# design.net
KiCad netlist of a schematic drawn in Altium Designer
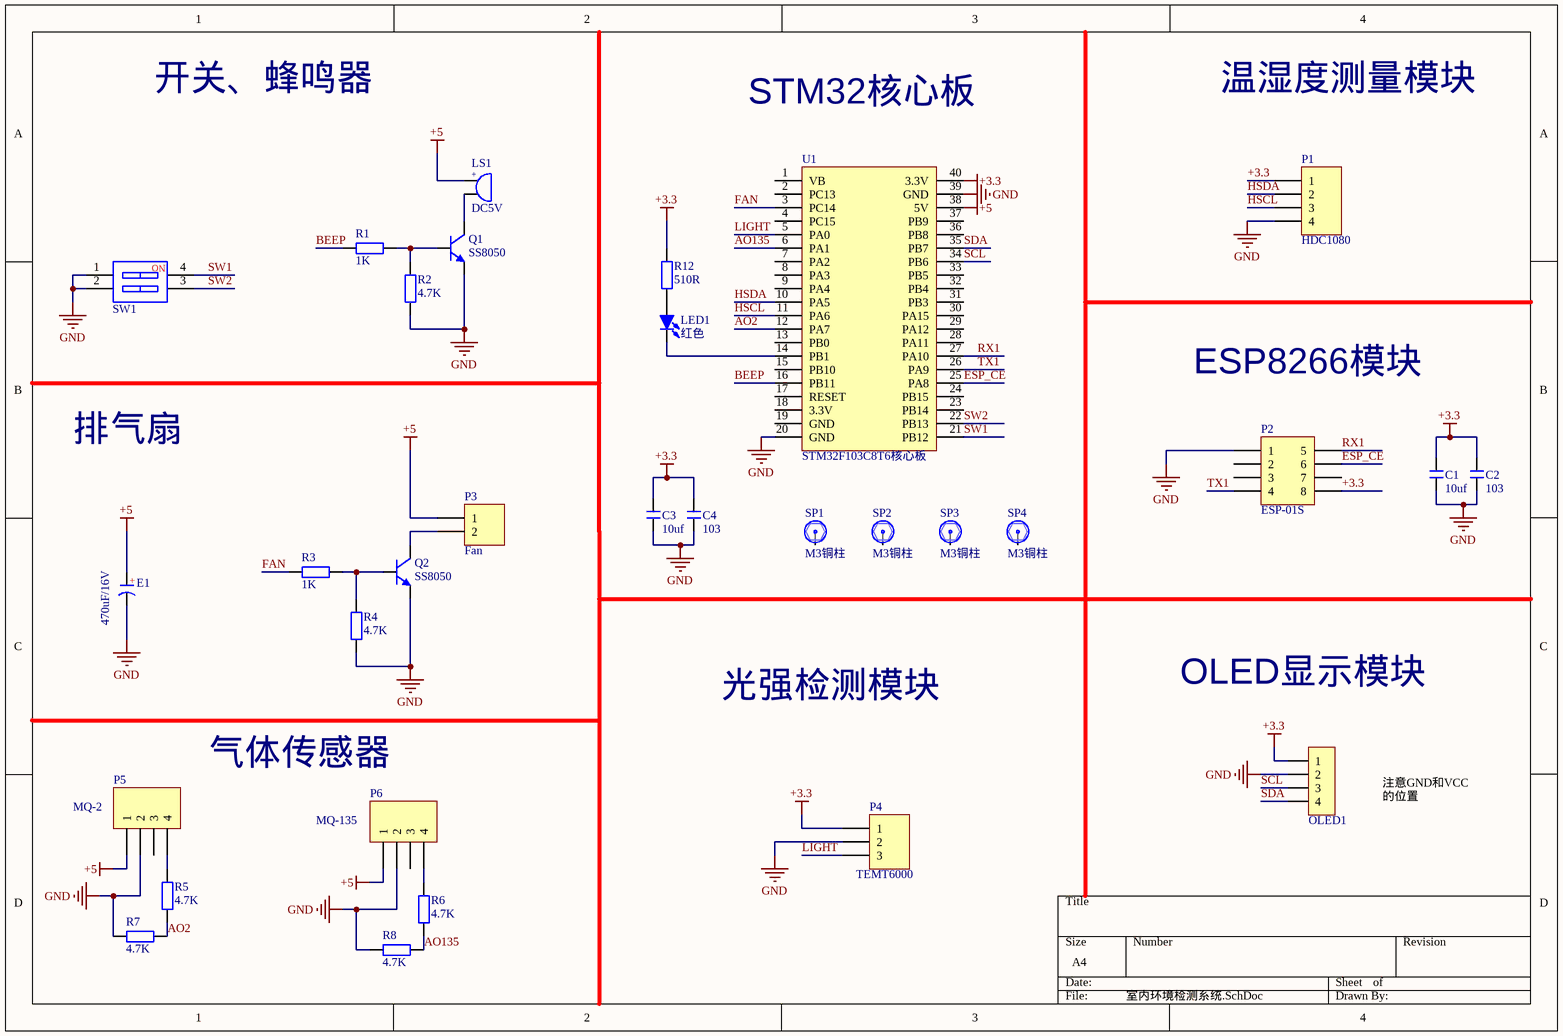
[diagram p0: 室内环境检测系统.SchDoc]

(export (version "E")
  (design (tool "Eeschema 10.0.6"))
  (components
    (comp (ref "C1")
      (value "10uf")
      (footprint "R 0805_M")
      (description "直插瓷片电容")
      (fields (field (name "版权归属") "源创客"))
      (libsource (lib "3.1   - 电阻-电容-电感") (part "C-CC"))
    )
    (comp (ref "C2")
      (value "103")
      (footprint "R 0805_M")
      (description "直插瓷片电容")
      (fields (field (name "版权归属") "源创客"))
      (libsource (lib "3.1   - 电阻-电容-电感") (part "C-CC"))
    )
    (comp (ref "C3")
      (value "10uf")
      (footprint "R 0805_M")
      (description "直插瓷片电容")
      (fields (field (name "版权归属") "源创客"))
      (libsource (lib "3.1   - 电阻-电容-电感") (part "C-CC"))
    )
    (comp (ref "C4")
      (value "103")
      (footprint "R 0805_M")
      (description "直插瓷片电容")
      (fields (field (name "版权归属") "源创客"))
      (libsource (lib "3.1   - 电阻-电容-电感") (part "C-CC"))
    )
    (comp (ref "E1")
      (value "470uF/16V")
      (footprint "CAP 2.0*5*11 - BK")
      (description "直插电解电容")
      (fields (field (name "版权归属") "源创客"))
      (libsource (lib "3.1   - 电阻-电容-电感") (part "C-CAP"))
    )
    (comp (ref "LED1")
      (value "红色")
      (footprint "LED 0805R")
      (description "贴片LED")
      (fields (field (name "版权归属") "源创客"))
      (libsource (lib "9.1   - LED") (part "LED-SMD"))
    )
    (comp (ref "LS1")
      (value "DC5V")
      (footprint "BEEP 5x9x5.5")
      (description "蜂鸣器")
      (fields (field (name "版权归属") "源创客"))
      (libsource (lib "15.1 - 未分类器件") (part "BEEP"))
    )
    (comp (ref "OLED1")
      (value "HDR-1X4")
      (footprint "HDR2.54-M-LI-4P")
      (description "4P接插件")
      (fields (field (name "版权归属") "源创客"))
      (libsource (lib "4.5   - 接插件-脚距2.54") (part "Header 4"))
    )
    (comp (ref "P1")
      (value "HDC1080")
      (footprint "HDR1X4")
      (description "Header, 4-Pin")
      (fields (field (name "PUBLISHER") "Altium Limited"))
      (libsource (lib "") (part "Header 4_1"))
    )
    (comp (ref "P2")
      (value "ESP-01S")
      (footprint "HDR2X4_CEN")
      (description "Header, 4-Pin, Dual row")
      (fields (field (name "PUBLISHER") "Altium Limited"))
      (libsource (lib "Miscellaneous Connectors") (part "Header 4X2A"))
    )
    (comp (ref "P3")
      (value "Fan")
      (footprint "HDR1X2H")
      (description "Header, 2-Pin, Right Angle")
      (fields (field (name "PUBLISHER") "Altium Limited"))
      (libsource (lib "Miscellaneous Connectors") (part "Header 2H"))
    )
    (comp (ref "P4")
      (value "TEMT6000")
      (footprint "HDR1X3")
      (description "Header, 3-Pin")
      (fields (field (name "PUBLISHER") "Altium Limited"))
      (libsource (lib "Miscellaneous Connectors") (part "Header 3"))
    )
    (comp (ref "P5")
      (value "MQ-2")
      (footprint "HDR1X4")
      (description "Header, 4-Pin")
      (fields (field (name "PUBLISHER") "Altium Limited"))
      (libsource (lib "Miscellaneous Connectors") (part "Header 4"))
    )
    (comp (ref "P6")
      (value "MQ-135")
      (footprint "HDR1X4")
      (description "Header, 4-Pin")
      (fields (field (name "PUBLISHER") "Altium Limited"))
      (libsource (lib "Miscellaneous Connectors") (part "Header 4"))
    )
    (comp (ref "Q1")
      (value "SS8050")
      (footprint "TO92A")
      (description "高频放大-NPN型")
      (fields (field (name "版权归属") "源创客"))
      (libsource (lib "6.2   - 三极管") (part "8050-DIP"))
    )
    (comp (ref "Q2")
      (value "SS8050")
      (footprint "TO92A")
      (description "高频放大-NPN型")
      (fields (field (name "版权归属") "源创客"))
      (libsource (lib "6.2   - 三极管") (part "8050-DIP"))
    )
    (comp (ref "R1")
      (value "1K")
      (footprint "R 0805_M")
      (description "直插色环电阻")
      (fields (field (name "版权归属") "源创客"))
      (libsource (lib "3.1   - 电阻-电容-电感") (part "R-CRR"))
    )
    (comp (ref "R2")
      (value "4.7K")
      (footprint "R 0805_M")
      (description "直插色环电阻")
      (fields (field (name "版权归属") "源创客"))
      (libsource (lib "3.1   - 电阻-电容-电感") (part "R-CRR"))
    )
    (comp (ref "R3")
      (value "1K")
      (footprint "R 0805_M")
      (description "直插色环电阻")
      (fields (field (name "版权归属") "源创客"))
      (libsource (lib "3.1   - 电阻-电容-电感") (part "R-CRR"))
    )
    (comp (ref "R4")
      (value "4.7K")
      (footprint "R 0805_M")
      (description "直插色环电阻")
      (fields (field (name "版权归属") "源创客"))
      (libsource (lib "3.1   - 电阻-电容-电感") (part "R-CRR"))
    )
    (comp (ref "R5")
      (value "4.7K")
      (footprint "R 0805_M")
      (description "直插色环电阻")
      (fields (field (name "版权归属") "源创客"))
      (libsource (lib "3.1   - 电阻-电容-电感") (part "R-CRR"))
    )
    (comp (ref "R6")
      (value "4.7K")
      (footprint "R 0805_M")
      (description "直插色环电阻")
      (fields (field (name "版权归属") "源创客"))
      (libsource (lib "3.1   - 电阻-电容-电感") (part "R-CRR"))
    )
    (comp (ref "R7")
      (value "4.7K")
      (footprint "R 0805_M")
      (description "直插色环电阻")
      (fields (field (name "版权归属") "源创客"))
      (libsource (lib "3.1   - 电阻-电容-电感") (part "R-CRR"))
    )
    (comp (ref "R8")
      (value "4.7K")
      (footprint "R 0805_M")
      (description "直插色环电阻")
      (fields (field (name "版权归属") "源创客"))
      (libsource (lib "3.1   - 电阻-电容-电感") (part "R-CRR"))
    )
    (comp (ref "R12")
      (value "510R")
      (footprint "R 0805_M")
      (description "直插色环电阻")
      (fields (field (name "版权归属") "源创客"))
      (libsource (lib "3.1   - 电阻-电容-电感") (part "R-CRR"))
    )
    (comp (ref "SP1")
      (value "M3铜柱")
      (footprint "M3x4_L")
      (description "铜柱")
      (fields (field (name "版权归属") "源创客"))
      (libsource (lib "15.1 - 未分类器件") (part "铜柱小焊盘"))
    )
    (comp (ref "SP2")
      (value "M3铜柱")
      (footprint "M3x4_L")
      (description "铜柱")
      (fields (field (name "版权归属") "源创客"))
      (libsource (lib "15.1 - 未分类器件") (part "铜柱小焊盘"))
    )
    (comp (ref "SP3")
      (value "M3铜柱")
      (footprint "M3x4_L")
      (description "铜柱")
      (fields (field (name "版权归属") "源创客"))
      (libsource (lib "15.1 - 未分类器件") (part "铜柱小焊盘"))
    )
    (comp (ref "SP4")
      (value "M3铜柱")
      (footprint "M3x4_L")
      (description "铜柱")
      (fields (field (name "版权归属") "源创客"))
      (libsource (lib "15.1 - 未分类器件") (part "铜柱小焊盘"))
    )
    (comp (ref "SW1")
      (value "CSW-2P")
      (footprint "CSW DIP-2P")
      (description "2路编码开关")
      (fields (field (name "版权归属") "源创客"))
      (libsource (lib "5.1   - 按键-开关") (part "CSW-2P"))
    )
    (comp (ref "U1")
      (value "STM32F103C8T6核心板")
      (footprint "DIP40-600_MH")
      (libsource (lib "STM32F103C8T6核心板") (part "STM32F103C8T6核心板"))
    )
  )
  (nets
    (net (code "1") (name "+3.3") (class "Default")
      (node (ref "C1") (pin "1") (pinfunction "1_1") (pintype "passive"))
      (node (ref "C2") (pin "1") (pinfunction "1_1") (pintype "passive"))
      (node (ref "C3") (pin "1") (pinfunction "1_1") (pintype "passive"))
      (node (ref "C4") (pin "1") (pinfunction "1_1") (pintype "passive"))
      (node (ref "OLED1") (pin "1") (pinfunction "1_1") (pintype "passive"))
      (node (ref "P1") (pin "1") (pinfunction "1_1") (pintype "passive"))
      (node (ref "P2") (pin "8") (pinfunction "8_8") (pintype "passive"))
      (node (ref "P4") (pin "1") (pinfunction "1_1") (pintype "passive"))
      (node (ref "R12") (pin "2") (pinfunction "2_2") (pintype "passive"))
      (node (ref "U1") (pin "40") (pinfunction "3.3V_40") (pintype "passive"))
    )
    (net (code "2") (name "+5") (class "Default")
      (node (ref "E1") (pin "1") (pinfunction "A_1") (pintype "passive"))
      (node (ref "LS1") (pin "1") (pinfunction "1_1") (pintype "passive"))
      (node (ref "P3") (pin "1") (pinfunction "1_1") (pintype "passive"))
      (node (ref "P5") (pin "1") (pinfunction "1_1") (pintype "passive"))
      (node (ref "P6") (pin "1") (pinfunction "1_1") (pintype "passive"))
      (node (ref "U1") (pin "38") (pinfunction "5V_38") (pintype "passive"))
    )
    (net (code "3") (name "/AO2") (class "Default")
      (node (ref "R5") (pin "2") (pinfunction "2_2") (pintype "passive"))
      (node (ref "R7") (pin "1") (pinfunction "1_1") (pintype "passive"))
      (node (ref "U1") (pin "12") (pinfunction "PA7_12") (pintype "passive"))
    )
    (net (code "4") (name "/AO135") (class "Default")
      (node (ref "R6") (pin "2") (pinfunction "2_2") (pintype "passive"))
      (node (ref "R8") (pin "1") (pinfunction "1_1") (pintype "passive"))
      (node (ref "U1") (pin "6") (pinfunction "PA1_6") (pintype "passive"))
    )
    (net (code "5") (name "/BEEP") (class "Default")
      (node (ref "R1") (pin "1") (pinfunction "1_1") (pintype "passive"))
      (node (ref "U1") (pin "16") (pinfunction "PB11_16") (pintype "passive"))
    )
    (net (code "6") (name "/ESP_CE") (class "Default")
      (node (ref "P2") (pin "6") (pinfunction "6_6") (pintype "passive"))
      (node (ref "U1") (pin "25") (pinfunction "PA8_25") (pintype "passive"))
    )
    (net (code "7") (name "/FAN") (class "Default")
      (node (ref "R3") (pin "1") (pinfunction "1_1") (pintype "passive"))
      (node (ref "U1") (pin "3") (pinfunction "PC14_3") (pintype "passive"))
    )
    (net (code "8") (name "/HSCL") (class "Default")
      (node (ref "P1") (pin "3") (pinfunction "3_3") (pintype "passive"))
      (node (ref "U1") (pin "11") (pinfunction "PA6_11") (pintype "passive"))
    )
    (net (code "9") (name "/HSDA") (class "Default")
      (node (ref "P1") (pin "2") (pinfunction "2_2") (pintype "passive"))
      (node (ref "U1") (pin "10") (pinfunction "PA5_10") (pintype "passive"))
    )
    (net (code "10") (name "/LIGHT") (class "Default")
      (node (ref "P4") (pin "3") (pinfunction "3_3") (pintype "passive"))
      (node (ref "U1") (pin "5") (pinfunction "PA0_5") (pintype "passive"))
    )
    (net (code "11") (name "/RX1") (class "Default")
      (node (ref "P2") (pin "5") (pinfunction "5_5") (pintype "passive"))
      (node (ref "U1") (pin "27") (pinfunction "PA10_27") (pintype "passive"))
    )
    (net (code "12") (name "/SCL") (class "Default")
      (node (ref "OLED1") (pin "3") (pinfunction "3_3") (pintype "passive"))
      (node (ref "U1") (pin "34") (pinfunction "PB6_34") (pintype "passive"))
    )
    (net (code "13") (name "/SDA") (class "Default")
      (node (ref "OLED1") (pin "4") (pinfunction "4_4") (pintype "passive"))
      (node (ref "U1") (pin "35") (pinfunction "PB7_35") (pintype "passive"))
    )
    (net (code "14") (name "/SW1") (class "Default")
      (node (ref "SW1") (pin "4") (pinfunction "4_4") (pintype "passive"))
      (node (ref "U1") (pin "21") (pinfunction "PB12_21") (pintype "passive"))
    )
    (net (code "15") (name "/SW2") (class "Default")
      (node (ref "SW1") (pin "3") (pinfunction "3_3") (pintype "passive"))
      (node (ref "U1") (pin "22") (pinfunction "PB13_22") (pintype "passive"))
    )
    (net (code "16") (name "/TX1") (class "Default")
      (node (ref "P2") (pin "4") (pinfunction "4_4") (pintype "passive"))
      (node (ref "U1") (pin "26") (pinfunction "PA9_26") (pintype "passive"))
    )
    (net (code "17") (name "GND") (class "Default")
      (node (ref "C1") (pin "2") (pinfunction "2_2") (pintype "passive"))
      (node (ref "C2") (pin "2") (pinfunction "2_2") (pintype "passive"))
      (node (ref "C3") (pin "2") (pinfunction "2_2") (pintype "passive"))
      (node (ref "C4") (pin "2") (pinfunction "2_2") (pintype "passive"))
      (node (ref "E1") (pin "2") (pinfunction "K_2") (pintype "passive"))
      (node (ref "OLED1") (pin "2") (pinfunction "2_2") (pintype "passive"))
      (node (ref "P1") (pin "4") (pinfunction "4_4") (pintype "passive"))
      (node (ref "P2") (pin "1") (pinfunction "1_1") (pintype "passive"))
      (node (ref "P4") (pin "2") (pinfunction "2_2") (pintype "passive"))
      (node (ref "P5") (pin "2") (pinfunction "2_2") (pintype "passive"))
      (node (ref "P6") (pin "2") (pinfunction "2_2") (pintype "passive"))
      (node (ref "Q1") (pin "1") (pinfunction "E_1") (pintype "passive"))
      (node (ref "Q2") (pin "1") (pinfunction "E_1") (pintype "passive"))
      (node (ref "R2") (pin "1") (pinfunction "1_1") (pintype "passive"))
      (node (ref "R4") (pin "1") (pinfunction "1_1") (pintype "passive"))
      (node (ref "R7") (pin "2") (pinfunction "2_2") (pintype "passive"))
      (node (ref "R8") (pin "2") (pinfunction "2_2") (pintype "passive"))
      (node (ref "SW1") (pin "1") (pinfunction "1_1") (pintype "passive"))
      (node (ref "SW1") (pin "2") (pinfunction "2_2") (pintype "passive"))
      (node (ref "U1") (pin "20") (pinfunction "GND_20") (pintype "passive"))
      (node (ref "U1") (pin "39") (pinfunction "GND_39") (pintype "passive"))
    )
    (net (code "18") (name "Net-(LED1-A)") (class "Default")
      (node (ref "LED1") (pin "1") (pinfunction "A_1") (pintype "passive"))
      (node (ref "R12") (pin "1") (pinfunction "1_1") (pintype "passive"))
    )
    (net (code "19") (name "Net-(LED1-K)") (class "Default")
      (node (ref "LED1") (pin "2") (pinfunction "K_2") (pintype "passive"))
      (node (ref "U1") (pin "14") (pinfunction "PB1_14") (pintype "passive"))
    )
    (net (code "20") (name "Net-(P5-Pad4)") (class "Default")
      (node (ref "P5") (pin "4") (pinfunction "4_4") (pintype "passive"))
      (node (ref "R5") (pin "1") (pinfunction "1_1") (pintype "passive"))
    )
    (net (code "21") (name "Net-(P6-Pad4)") (class "Default")
      (node (ref "P6") (pin "4") (pinfunction "4_4") (pintype "passive"))
      (node (ref "R6") (pin "1") (pinfunction "1_1") (pintype "passive"))
    )
    (net (code "22") (name "Net-(Q1-B)") (class "Default")
      (node (ref "Q1") (pin "2") (pinfunction "B_2") (pintype "passive"))
      (node (ref "R1") (pin "2") (pinfunction "2_2") (pintype "passive"))
      (node (ref "R2") (pin "2") (pinfunction "2_2") (pintype "passive"))
    )
    (net (code "23") (name "Net-(Q1-C)") (class "Default")
      (node (ref "LS1") (pin "2") (pinfunction "2_2") (pintype "passive"))
      (node (ref "Q1") (pin "3") (pinfunction "C_3") (pintype "passive"))
    )
    (net (code "24") (name "Net-(Q2-B)") (class "Default")
      (node (ref "Q2") (pin "2") (pinfunction "B_2") (pintype "passive"))
      (node (ref "R3") (pin "2") (pinfunction "2_2") (pintype "passive"))
      (node (ref "R4") (pin "2") (pinfunction "2_2") (pintype "passive"))
    )
    (net (code "25") (name "Net-(Q2-C)") (class "Default")
      (node (ref "P3") (pin "2") (pinfunction "2_2") (pintype "passive"))
      (node (ref "Q2") (pin "3") (pinfunction "C_3") (pintype "passive"))
    )
    (net (code "26") (name "unconnected-(P2-Pad2)") (class "Default")
      (node (ref "P2") (pin "2") (pinfunction "2_2") (pintype "passive"))
    )
    (net (code "27") (name "unconnected-(P2-Pad3)") (class "Default")
      (node (ref "P2") (pin "3") (pinfunction "3_3") (pintype "passive"))
    )
    (net (code "28") (name "unconnected-(P2-Pad7)") (class "Default")
      (node (ref "P2") (pin "7") (pinfunction "7_7") (pintype "passive"))
    )
    (net (code "29") (name "unconnected-(P5-Pad3)") (class "Default")
      (node (ref "P5") (pin "3") (pinfunction "3_3") (pintype "passive"))
    )
    (net (code "30") (name "unconnected-(P6-Pad3)") (class "Default")
      (node (ref "P6") (pin "3") (pinfunction "3_3") (pintype "passive"))
    )
    (net (code "31") (name "unconnected-(SP1-Pad1)") (class "Default")
      (node (ref "SP1") (pin "1") (pinfunction "1_1") (pintype "passive"))
    )
    (net (code "32") (name "unconnected-(SP2-Pad1)") (class "Default")
      (node (ref "SP2") (pin "1") (pinfunction "1_1") (pintype "passive"))
    )
    (net (code "33") (name "unconnected-(SP3-Pad1)") (class "Default")
      (node (ref "SP3") (pin "1") (pinfunction "1_1") (pintype "passive"))
    )
    (net (code "34") (name "unconnected-(SP4-Pad1)") (class "Default")
      (node (ref "SP4") (pin "1") (pinfunction "1_1") (pintype "passive"))
    )
    (net (code "35") (name "unconnected-(U1-3.3V-Pad18)") (class "Default")
      (node (ref "U1") (pin "18") (pinfunction "3.3V_18") (pintype "passive"))
    )
    (net (code "36") (name "unconnected-(U1-GND-Pad19)") (class "Default")
      (node (ref "U1") (pin "19") (pinfunction "GND_19") (pintype "passive"))
    )
    (net (code "37") (name "unconnected-(U1-PA2-Pad7)") (class "Default")
      (node (ref "U1") (pin "7") (pinfunction "PA2_7") (pintype "passive"))
    )
    (net (code "38") (name "unconnected-(U1-PA3-Pad8)") (class "Default")
      (node (ref "U1") (pin "8") (pinfunction "PA3_8") (pintype "passive"))
    )
    (net (code "39") (name "unconnected-(U1-PA4-Pad9)") (class "Default")
      (node (ref "U1") (pin "9") (pinfunction "PA4_9") (pintype "passive"))
    )
    (net (code "40") (name "unconnected-(U1-PA11-Pad28)") (class "Default")
      (node (ref "U1") (pin "28") (pinfunction "PA11_28") (pintype "passive"))
    )
    (net (code "41") (name "unconnected-(U1-PA12-Pad29)") (class "Default")
      (node (ref "U1") (pin "29") (pinfunction "PA12_29") (pintype "passive"))
    )
    (net (code "42") (name "unconnected-(U1-PA15-Pad30)") (class "Default")
      (node (ref "U1") (pin "30") (pinfunction "PA15_30") (pintype "passive"))
    )
    (net (code "43") (name "unconnected-(U1-PB0-Pad13)") (class "Default")
      (node (ref "U1") (pin "13") (pinfunction "PB0_13") (pintype "passive"))
    )
    (net (code "44") (name "unconnected-(U1-PB3-Pad31)") (class "Default")
      (node (ref "U1") (pin "31") (pinfunction "PB3_31") (pintype "passive"))
    )
    (net (code "45") (name "unconnected-(U1-PB4-Pad32)") (class "Default")
      (node (ref "U1") (pin "32") (pinfunction "PB4_32") (pintype "passive"))
    )
    (net (code "46") (name "unconnected-(U1-PB5-Pad33)") (class "Default")
      (node (ref "U1") (pin "33") (pinfunction "PB5_33") (pintype "passive"))
    )
    (net (code "47") (name "unconnected-(U1-PB8-Pad36)") (class "Default")
      (node (ref "U1") (pin "36") (pinfunction "PB8_36") (pintype "passive"))
    )
    (net (code "48") (name "unconnected-(U1-PB9-Pad37)") (class "Default")
      (node (ref "U1") (pin "37") (pinfunction "PB9_37") (pintype "passive"))
    )
    (net (code "49") (name "unconnected-(U1-PB10-Pad15)") (class "Default")
      (node (ref "U1") (pin "15") (pinfunction "PB10_15") (pintype "passive"))
    )
    (net (code "50") (name "unconnected-(U1-PB14-Pad23)") (class "Default")
      (node (ref "U1") (pin "23") (pinfunction "PB14_23") (pintype "passive"))
    )
    (net (code "51") (name "unconnected-(U1-PB15-Pad24)") (class "Default")
      (node (ref "U1") (pin "24") (pinfunction "PB15_24") (pintype "passive"))
    )
    (net (code "52") (name "unconnected-(U1-PC13-Pad2)") (class "Default")
      (node (ref "U1") (pin "2") (pinfunction "PC13_2") (pintype "passive"))
    )
    (net (code "53") (name "unconnected-(U1-PC15-Pad4)") (class "Default")
      (node (ref "U1") (pin "4") (pinfunction "PC15_4") (pintype "passive"))
    )
    (net (code "54") (name "unconnected-(U1-RESET-Pad17)") (class "Default")
      (node (ref "U1") (pin "17") (pinfunction "RESET_17") (pintype "passive"))
    )
    (net (code "55") (name "unconnected-(U1-VB-Pad1)") (class "Default")
      (node (ref "U1") (pin "1") (pinfunction "VB_1") (pintype "passive"))
    )
  )
)
